# noroshi_LoRa_RAK.net
KiCad netlist of a schematic drawn in EAGLE
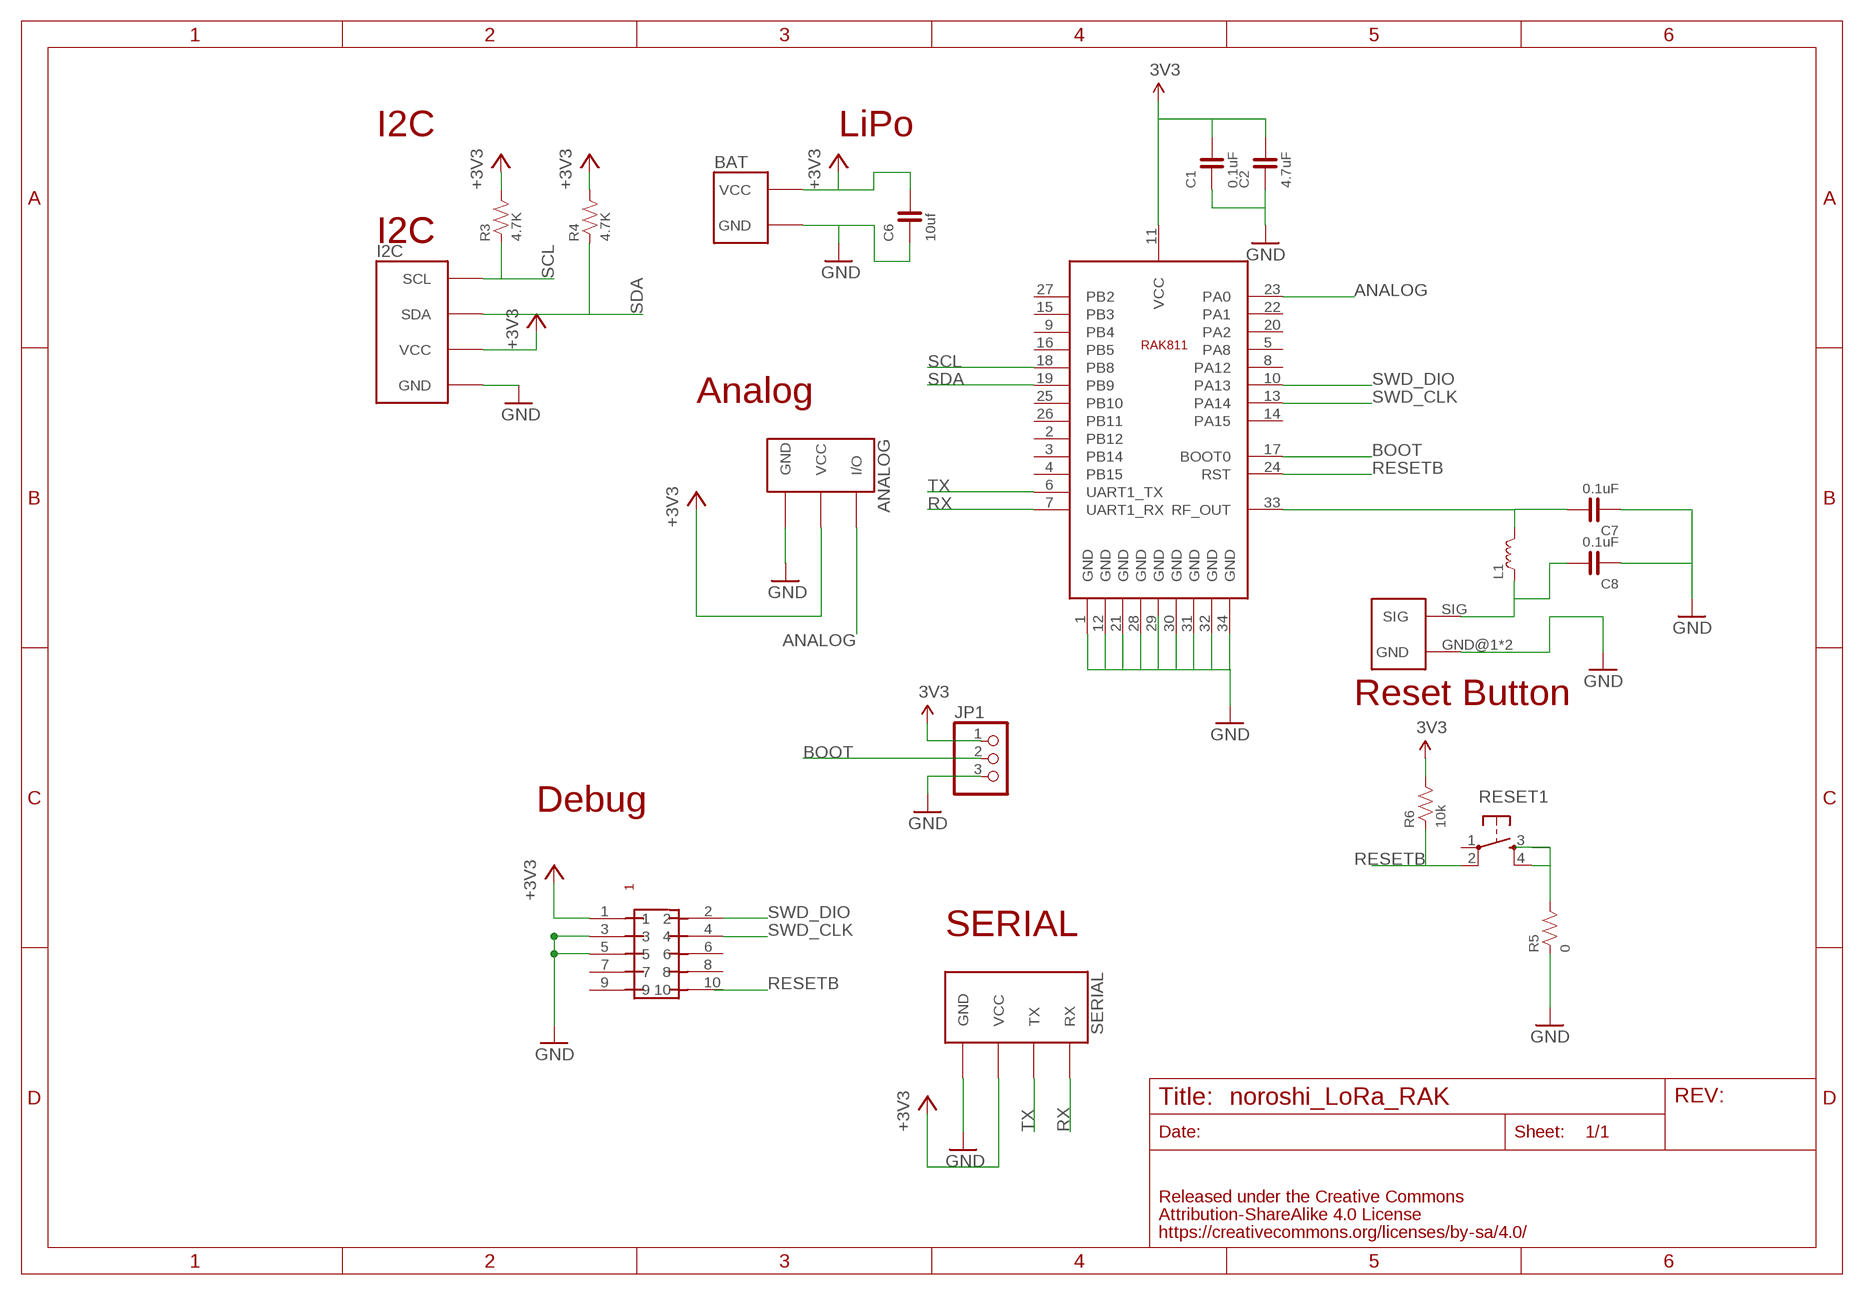
[diagram p0: schematic, sheet 1]

(export (version "E")
  (design (tool "Eeschema 10.0.6"))
  (components
    (comp (ref "ANALOG")
      (value "FABO_BRICK_3PIN-S03B-PASK-2_LONG")
      (footprint "eagle-import:FABO_BRICK_3PIN_S03B-PASK-2_LONG")
      (libsource (lib "eagle-import") (part "FABO_BRICK_3PIN-S03B-PASK-2_LONG"))
    )
    (comp (ref "BAT")
      (value "FABO_BRICK_2PIN_SIDE")
      (footprint "eagle-import:FABO_BRICK_2PIN_S02B−PASK-2_SILK")
      (libsource (lib "eagle-import") (part "FABO_BRICK_2PIN_SIDE"))
    )
    (comp (ref "C1")
      (value "0.1uF")
      (footprint "eagle-import:0603-NARROW")
      (libsource (lib "eagle-import") (part "CAPACITOR-0603_NARROW"))
    )
    (comp (ref "C2")
      (value "4.7uF")
      (footprint "eagle-import:0603-NARROW")
      (libsource (lib "eagle-import") (part "CAPACITOR-0603_NARROW"))
    )
    (comp (ref "C6")
      (value "10uf")
      (footprint "eagle-import:0603")
      (libsource (lib "eagle-import") (part "CAPACITOR-0603"))
    )
    (comp (ref "C7")
      (value "0.1uF")
      (footprint "eagle-import:0603-NARROW")
      (libsource (lib "eagle-import") (part "CAPACITOR-0603_NARROW"))
    )
    (comp (ref "C8")
      (value "0.1uF")
      (footprint "eagle-import:0603-NARROW")
      (libsource (lib "eagle-import") (part "CAPACITOR-0603_NARROW"))
    )
    (comp (ref "I2C")
      (value "FABO_BRICK_I2C-S04B-PASK-2_LONG")
      (footprint "eagle-import:FABO_BRICK_I2C_S04B-PASK-2_LONG")
      (libsource (lib "eagle-import") (part "FABO_BRICK_I2C-S04B-PASK-2_LONG"))
    )
    (comp (ref "JP1")
      (value "PINHD-1X3")
      (footprint "eagle-import:1X03")
      (libsource (lib "eagle-import") (part "PINHD-1X3"))
    )
    (comp (ref "L1")
      (value "COIL-0603")
      (footprint "eagle-import:0603")
      (libsource (lib "eagle-import") (part "COIL-0603"))
    )
    (comp (ref "R3")
      (value "4.7K")
      (footprint "eagle-import:0603")
      (libsource (lib "eagle-import") (part "RESISTOR-0603"))
    )
    (comp (ref "R4")
      (value "4.7K")
      (footprint "eagle-import:0603")
      (libsource (lib "eagle-import") (part "RESISTOR-0603"))
    )
    (comp (ref "R5")
      (value "0")
      (footprint "eagle-import:0603-NARROW")
      (libsource (lib "eagle-import") (part "RESISTOR-0603-NARROW"))
    )
    (comp (ref "R6")
      (value "10k")
      (footprint "eagle-import:0603-NARROW")
      (libsource (lib "eagle-import") (part "RESISTOR-0603-NARROW"))
    )
    (comp (ref "RESET1")
      (value "TACT-SWITCH-SMD_KMR2")
      (footprint "eagle-import:KMR2")
      (libsource (lib "eagle-import") (part "TACT-SWITCH-SMD_KMR2"))
    )
    (comp (ref "SERIAL")
      (value "FABO_BRICK_SERIAL-S04B-PASK-2_LONG")
      (footprint "eagle-import:FABO_BRICK_SERIAL_S04B-PASK-2_LONG")
      (libsource (lib "eagle-import") (part "FABO_BRICK_SERIAL-S04B-PASK-2_LONG"))
    )
    (comp (ref "U$2")
      (value "RAK811")
      (footprint "eagle-import:RAK811")
      (libsource (lib "eagle-import") (part "RAK811"))
    )
    (comp (ref "U$8")
      (value "PIN-HEADER-SMT(1.27MM)2X5")
      (footprint "eagle-import:PIN-HEADER-SMT(1.27MM)2X5")
      (libsource (lib "eagle-import") (part "PIN-HEADER-SMT(1.27MM)2X5"))
    )
    (comp (ref "UF1")
      (value "HIROSE-U.FL")
      (footprint "eagle-import:HIROSE-UF.L")
      (libsource (lib "eagle-import") (part "HIROSE-U.FL"))
    )
  )
  (nets
    (net (code "1") (name "+3V3") (class "Default")
      (node (ref "ANALOG") (pin "VCC") (pinfunction "VCC_VCC") (pintype "bidirectional"))
      (node (ref "BAT") (pin "VCC") (pinfunction "VCC_VCC") (pintype "bidirectional"))
      (node (ref "C6") (pin "2") (pinfunction "2_2") (pintype "passive"))
      (node (ref "I2C") (pin "VCC") (pinfunction "VCC_VCC") (pintype "bidirectional"))
      (node (ref "R3") (pin "2") (pinfunction "2_2") (pintype "bidirectional"))
      (node (ref "R4") (pin "2") (pinfunction "2_2") (pintype "bidirectional"))
      (node (ref "SERIAL") (pin "VCC") (pinfunction "VCC_VCC") (pintype "bidirectional"))
      (node (ref "U$8") (pin "1") (pinfunction "1_1") (pintype "bidirectional"))
    )
    (net (code "2") (name "/ANALOG") (class "Default")
      (node (ref "ANALOG") (pin "I/O") (pinfunction "I/O_I/O") (pintype "bidirectional"))
      (node (ref "U$2") (pin "23") (pinfunction "PA0_23") (pintype "bidirectional"))
    )
    (net (code "3") (name "/BOOT") (class "Default")
      (node (ref "JP1") (pin "2") (pinfunction "2_2") (pintype "passive"))
      (node (ref "U$2") (pin "17") (pinfunction "BOOT0_17") (pintype "bidirectional"))
    )
    (net (code "4") (name "/RESETB") (class "Default")
      (node (ref "R6") (pin "1") (pinfunction "1_1") (pintype "bidirectional"))
      (node (ref "RESET1") (pin "2") (pinfunction "2_2") (pintype "passive"))
      (node (ref "U$2") (pin "24") (pinfunction "RST_24") (pintype "bidirectional"))
      (node (ref "U$8") (pin "10") (pinfunction "10_10") (pintype "bidirectional"))
    )
    (net (code "5") (name "/RX") (class "Default")
      (node (ref "SERIAL") (pin "RX") (pinfunction "RX_RX") (pintype "bidirectional"))
      (node (ref "U$2") (pin "7") (pinfunction "UART1_RX_7") (pintype "bidirectional"))
    )
    (net (code "6") (name "/SCL") (class "Default")
      (node (ref "I2C") (pin "SCL") (pinfunction "SCL_SCL") (pintype "bidirectional"))
      (node (ref "R3") (pin "1") (pinfunction "1_1") (pintype "bidirectional"))
      (node (ref "U$2") (pin "18") (pinfunction "PB8_18") (pintype "bidirectional"))
    )
    (net (code "7") (name "/SDA") (class "Default")
      (node (ref "I2C") (pin "SDA") (pinfunction "SDA_SDA") (pintype "bidirectional"))
      (node (ref "R4") (pin "1") (pinfunction "1_1") (pintype "bidirectional"))
      (node (ref "U$2") (pin "19") (pinfunction "PB9_19") (pintype "bidirectional"))
    )
    (net (code "8") (name "/SWD_CLK") (class "Default")
      (node (ref "U$2") (pin "13") (pinfunction "PA14_13") (pintype "bidirectional"))
      (node (ref "U$8") (pin "4") (pinfunction "4_4") (pintype "bidirectional"))
    )
    (net (code "9") (name "/SWD_DIO") (class "Default")
      (node (ref "U$2") (pin "10") (pinfunction "PA13_10") (pintype "bidirectional"))
      (node (ref "U$8") (pin "2") (pinfunction "2_2") (pintype "bidirectional"))
    )
    (net (code "10") (name "/TX") (class "Default")
      (node (ref "SERIAL") (pin "TX") (pinfunction "TX_TX") (pintype "bidirectional"))
      (node (ref "U$2") (pin "6") (pinfunction "UART1_TX_6") (pintype "bidirectional"))
    )
    (net (code "11") (name "3V3") (class "Default")
      (node (ref "C1") (pin "2") (pinfunction "2_2") (pintype "passive"))
      (node (ref "C2") (pin "2") (pinfunction "2_2") (pintype "passive"))
      (node (ref "JP1") (pin "1") (pinfunction "1_1") (pintype "passive"))
      (node (ref "R6") (pin "2") (pinfunction "2_2") (pintype "bidirectional"))
      (node (ref "U$2") (pin "11") (pinfunction "VCC_11") (pintype "bidirectional"))
    )
    (net (code "12") (name "GND") (class "Default")
      (node (ref "ANALOG") (pin "GND") (pinfunction "GND_GND") (pintype "bidirectional"))
      (node (ref "BAT") (pin "GND") (pinfunction "GND_GND") (pintype "bidirectional"))
      (node (ref "C1") (pin "1") (pinfunction "1_1") (pintype "passive"))
      (node (ref "C2") (pin "1") (pinfunction "1_1") (pintype "passive"))
      (node (ref "C6") (pin "1") (pinfunction "1_1") (pintype "passive"))
      (node (ref "C7") (pin "1") (pinfunction "1_1") (pintype "passive"))
      (node (ref "C8") (pin "1") (pinfunction "1_1") (pintype "passive"))
      (node (ref "I2C") (pin "GND") (pinfunction "GND_GND") (pintype "bidirectional"))
      (node (ref "JP1") (pin "3") (pinfunction "3_3") (pintype "passive"))
      (node (ref "R5") (pin "1") (pinfunction "1_1") (pintype "bidirectional"))
      (node (ref "SERIAL") (pin "GND") (pinfunction "GND_GND") (pintype "bidirectional"))
      (node (ref "U$2") (pin "1") (pinfunction "GND_1") (pintype "bidirectional"))
      (node (ref "U$2") (pin "12") (pinfunction "GND_12") (pintype "bidirectional"))
      (node (ref "U$2") (pin "21") (pinfunction "GND_21") (pintype "bidirectional"))
      (node (ref "U$2") (pin "28") (pinfunction "GND_28") (pintype "bidirectional"))
      (node (ref "U$2") (pin "30") (pinfunction "GND_30") (pintype "bidirectional"))
      (node (ref "U$2") (pin "31") (pinfunction "GND_31") (pintype "bidirectional"))
      (node (ref "U$2") (pin "32") (pinfunction "GND_32") (pintype "bidirectional"))
      (node (ref "U$2") (pin "34") (pinfunction "GND_34") (pintype "bidirectional"))
      (node (ref "U$8") (pin "3") (pinfunction "3_3") (pintype "bidirectional"))
      (node (ref "U$8") (pin "5") (pinfunction "5_5") (pintype "bidirectional"))
      (node (ref "UF1") (pin "GND@1") (pinfunction "GND_GND@1") (pintype "bidirectional"))
      (node (ref "UF1") (pin "GND@2") (pinfunction "GND_GND@2") (pintype "bidirectional"))
    )
    (net (code "13") (name "Net-(C8-Pad2)") (class "Default")
      (node (ref "C8") (pin "2") (pinfunction "2_2") (pintype "passive"))
      (node (ref "L1") (pin "1") (pinfunction "1_1") (pintype "bidirectional"))
      (node (ref "UF1") (pin "SIG") (pinfunction "SIG_SIG") (pintype "bidirectional"))
    )
    (net (code "14") (name "Net-(R5-Pad2)") (class "Default")
      (node (ref "R5") (pin "2") (pinfunction "2_2") (pintype "bidirectional"))
      (node (ref "RESET1") (pin "3") (pinfunction "3_3") (pintype "passive"))
      (node (ref "RESET1") (pin "4") (pinfunction "4_4") (pintype "passive"))
    )
    (net (code "15") (name "Net-(U$2-RF_OUT)") (class "Default")
      (node (ref "C7") (pin "2") (pinfunction "2_2") (pintype "passive"))
      (node (ref "L1") (pin "2") (pinfunction "2_2") (pintype "bidirectional"))
      (node (ref "U$2") (pin "33") (pinfunction "RF_OUT_33") (pintype "bidirectional"))
    )
    (net (code "16") (name "unconnected-(RESET1-Pad1)") (class "Default")
      (node (ref "RESET1") (pin "1") (pinfunction "1_1") (pintype "passive"))
    )
    (net (code "17") (name "unconnected-(U$2-GND-Pad29)") (class "Default")
      (node (ref "U$2") (pin "29") (pinfunction "GND_29") (pintype "bidirectional"))
    )
    (net (code "18") (name "unconnected-(U$2-PA1-Pad22)") (class "Default")
      (node (ref "U$2") (pin "22") (pinfunction "PA1_22") (pintype "bidirectional"))
    )
    (net (code "19") (name "unconnected-(U$2-PA2-Pad20)") (class "Default")
      (node (ref "U$2") (pin "20") (pinfunction "PA2_20") (pintype "bidirectional"))
    )
    (net (code "20") (name "unconnected-(U$2-PA8-Pad5)") (class "Default")
      (node (ref "U$2") (pin "5") (pinfunction "PA8_5") (pintype "bidirectional"))
    )
    (net (code "21") (name "unconnected-(U$2-PA12-Pad8)") (class "Default")
      (node (ref "U$2") (pin "8") (pinfunction "PA12_8") (pintype "bidirectional"))
    )
    (net (code "22") (name "unconnected-(U$2-PA15-Pad14)") (class "Default")
      (node (ref "U$2") (pin "14") (pinfunction "PA15_14") (pintype "bidirectional"))
    )
    (net (code "23") (name "unconnected-(U$2-PB2-Pad27)") (class "Default")
      (node (ref "U$2") (pin "27") (pinfunction "PB2_27") (pintype "bidirectional"))
    )
    (net (code "24") (name "unconnected-(U$2-PB3-Pad15)") (class "Default")
      (node (ref "U$2") (pin "15") (pinfunction "PB3_15") (pintype "bidirectional"))
    )
    (net (code "25") (name "unconnected-(U$2-PB4-Pad9)") (class "Default")
      (node (ref "U$2") (pin "9") (pinfunction "PB4_9") (pintype "bidirectional"))
    )
    (net (code "26") (name "unconnected-(U$2-PB5-Pad16)") (class "Default")
      (node (ref "U$2") (pin "16") (pinfunction "PB5_16") (pintype "bidirectional"))
    )
    (net (code "27") (name "unconnected-(U$2-PB10-Pad25)") (class "Default")
      (node (ref "U$2") (pin "25") (pinfunction "PB10_25") (pintype "bidirectional"))
    )
    (net (code "28") (name "unconnected-(U$2-PB11-Pad26)") (class "Default")
      (node (ref "U$2") (pin "26") (pinfunction "PB11_26") (pintype "bidirectional"))
    )
    (net (code "29") (name "unconnected-(U$2-PB12-Pad2)") (class "Default")
      (node (ref "U$2") (pin "2") (pinfunction "PB12_2") (pintype "bidirectional"))
    )
    (net (code "30") (name "unconnected-(U$2-PB14-Pad3)") (class "Default")
      (node (ref "U$2") (pin "3") (pinfunction "PB14_3") (pintype "bidirectional"))
    )
    (net (code "31") (name "unconnected-(U$2-PB15-Pad4)") (class "Default")
      (node (ref "U$2") (pin "4") (pinfunction "PB15_4") (pintype "bidirectional"))
    )
    (net (code "32") (name "unconnected-(U$8-Pad6)") (class "Default")
      (node (ref "U$8") (pin "6") (pinfunction "6_6") (pintype "bidirectional"))
    )
    (net (code "33") (name "unconnected-(U$8-Pad7)") (class "Default")
      (node (ref "U$8") (pin "7") (pinfunction "7_7") (pintype "bidirectional"))
    )
    (net (code "34") (name "unconnected-(U$8-Pad8)") (class "Default")
      (node (ref "U$8") (pin "8") (pinfunction "8_8") (pintype "bidirectional"))
    )
    (net (code "35") (name "unconnected-(U$8-Pad9)") (class "Default")
      (node (ref "U$8") (pin "9") (pinfunction "9_9") (pintype "bidirectional"))
    )
  )
)
